# Sheet1.net
KiCad netlist of a schematic drawn in Altium Designer
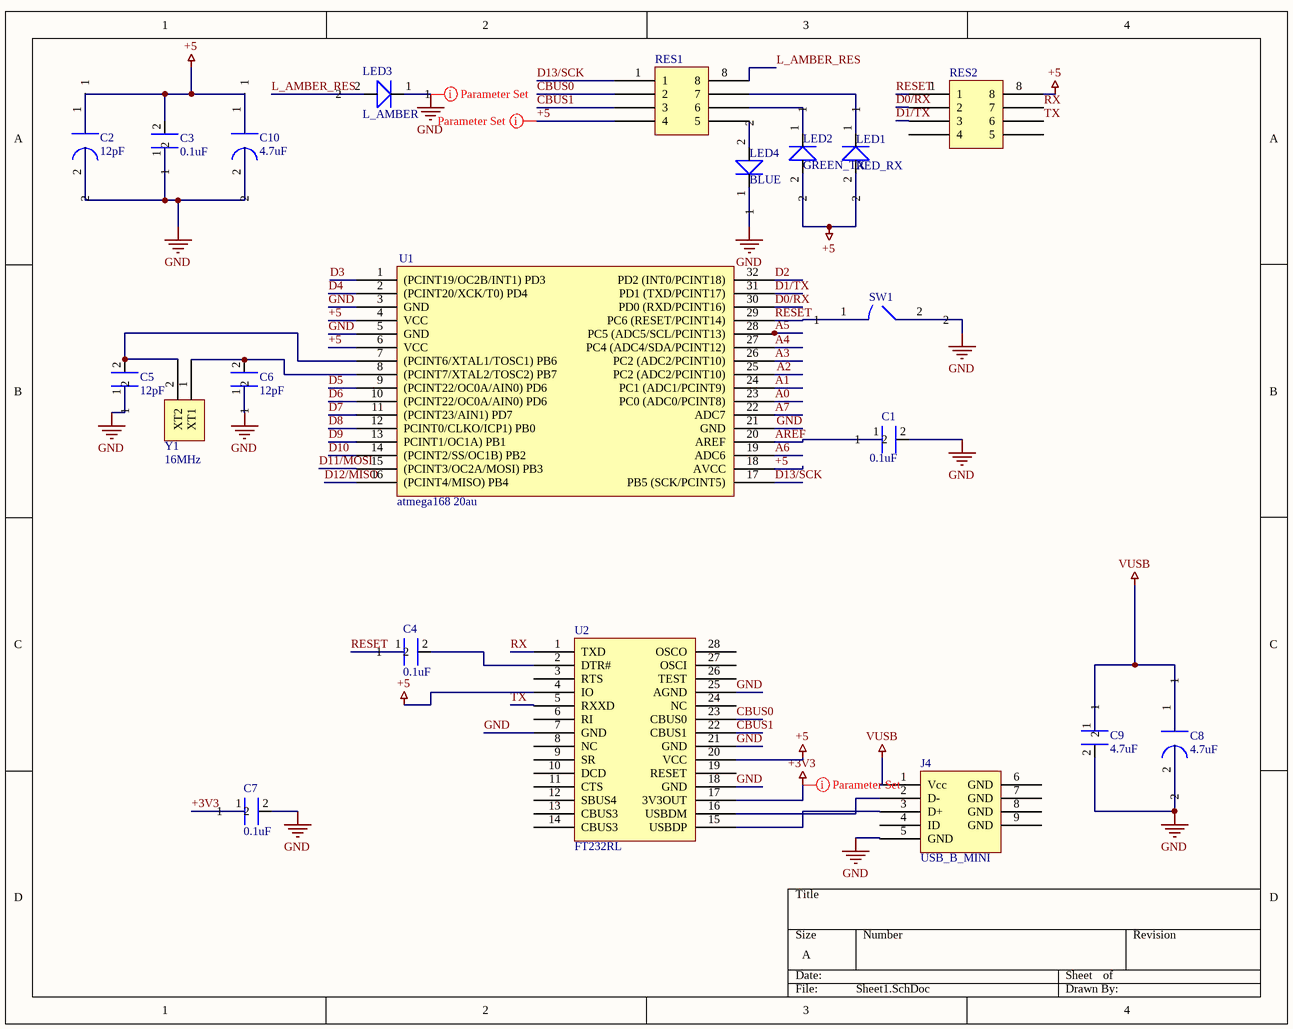
[diagram p0: Sheet1.SchDoc]

(export (version "E")
  (design (tool "Eeschema 10.0.6"))
  (components
    (comp (ref "C1") (value "0.1uF") (footprint "Capacitor0805") (libsource (lib "cap") (part "Component_1")))
    (comp (ref "C2")
      (value "12pF")
      (footprint "tantalum cap 7343")
      (libsource (lib "cap_pol") (part "Component_1"))
    )
    (comp (ref "C3") (value "0.1uF") (footprint "Capacitor0805") (libsource (lib "cap") (part "Component_1")))
    (comp (ref "C4") (value "0.1uF") (footprint "Capacitor0805") (libsource (lib "cap") (part "Component_1")))
    (comp (ref "C5") (value "12pF") (footprint "Capacitor0805") (libsource (lib "cap") (part "Component_1")))
    (comp (ref "C6") (value "12pF") (footprint "Capacitor0805") (libsource (lib "cap") (part "Component_1")))
    (comp (ref "C7") (value "0.1uF") (footprint "Capacitor0805") (libsource (lib "cap") (part "Component_1")))
    (comp (ref "C8")
      (value "4.7uF")
      (footprint "tantalum cap 7343")
      (libsource (lib "cap_pol") (part "Component_1"))
    )
    (comp (ref "C9") (value "4.7uF") (footprint "Capacitor0805") (libsource (lib "cap") (part "Component_1")))
    (comp (ref "C10")
      (value "4.7uF")
      (footprint "tantalum cap 7343")
      (libsource (lib "cap_pol") (part "Component_1"))
    )
    (comp (ref "J4")
      (value "USB_B_MINI")
      (footprint "Mini B usb")
      (libsource (lib "mini_USB_connector") (part "Component_1"))
    )
    (comp (ref "LED1") (value "RED_RX") (footprint "LED 0805") (libsource (lib "LED") (part "Component_1")))
    (comp (ref "LED2") (value "GREEN_TX") (footprint "LED 0805") (libsource (lib "LED") (part "Component_1")))
    (comp (ref "LED3") (value "L_AMBER") (footprint "LED 0805") (libsource (lib "LED") (part "Component_1")))
    (comp (ref "LED4") (value "BLUE") (footprint "LED 0805") (libsource (lib "LED") (part "Component_1")))
    (comp (ref "RES1")
      (value "Component_1")
      (footprint "Quad 4 res array")
      (libsource (lib "RES_ARRAY") (part "Component_1"))
    )
    (comp (ref "RES2")
      (value "Component_1")
      (footprint "Quad 4 res array")
      (libsource (lib "RES_ARRAY") (part "Component_1"))
    )
    (comp (ref "SW1") (value "RESET") (footprint "switch") (libsource (lib "switch") (part "Component_1")))
    (comp (ref "U1")
      (value "atmega168 20au")
      (footprint "Quad32")
      (libsource (lib "atmega16820au") (part "atmega168 20au"))
    )
    (comp (ref "U2")
      (value "FT232RL")
      (footprint "Quad28 FTDI")
      (libsource (lib "_REEL") (part "Component_1"))
    )
    (comp (ref "Y1") (value "16MHz") (footprint "TH XT") (libsource (lib "osci") (part "Component_1")))
  )
  (nets
    (net (code "1") (name "+3V3") (class "Default")
      (node (ref "C7") (pin "1") (pinfunction "1_1") (pintype "passive"))
      (node (ref "U2") (pin "17") (pinfunction "3V3OUT_17") (pintype "passive"))
    )
    (net (code "2") (name "+5") (class "Default")
      (node (ref "C10") (pin "1") (pinfunction "1_1") (pintype "passive"))
      (node (ref "C2") (pin "1") (pinfunction "1_1") (pintype "passive"))
      (node (ref "C3") (pin "2") (pinfunction "2_2") (pintype "passive"))
      (node (ref "LED1") (pin "2") (pinfunction "2_2") (pintype "passive"))
      (node (ref "LED2") (pin "2") (pinfunction "2_2") (pintype "passive"))
      (node (ref "RES1") (pin "4") (pinfunction "4_4") (pintype "passive"))
      (node (ref "RES2") (pin "8") (pinfunction "8_8") (pintype "passive"))
      (node (ref "U1") (pin "18") (pinfunction "AVCC_18") (pintype "passive"))
      (node (ref "U1") (pin "4") (pinfunction "VCC_4") (pintype "passive"))
      (node (ref "U1") (pin "6") (pinfunction "VCC_6") (pintype "passive"))
      (node (ref "U2") (pin "20") (pinfunction "VCC_20") (pintype "passive"))
      (node (ref "U2") (pin "4") (pinfunction "IO_4") (pintype "passive"))
    )
    (net (code "3") (name "/A0") (class "Default")
      (node (ref "U1") (pin "23") (pinfunction "PC0_(ADC0/PCINT8)_23") (pintype "passive"))
    )
    (net (code "4") (name "/A1") (class "Default")
      (node (ref "U1") (pin "24") (pinfunction "PC1_(ADC1/PCINT9)_24") (pintype "passive"))
    )
    (net (code "5") (name "/A2") (class "Default")
      (node (ref "U1") (pin "25") (pinfunction "PC2_(ADC2/PCINT10)_25") (pintype "passive"))
    )
    (net (code "6") (name "/A3") (class "Default")
      (node (ref "U1") (pin "26") (pinfunction "PC2_(ADC2/PCINT10)_26") (pintype "passive"))
    )
    (net (code "7") (name "/A4") (class "Default")
      (node (ref "U1") (pin "27") (pinfunction "PC4_(ADC4/SDA/PCINT12)_27") (pintype "passive"))
    )
    (net (code "8") (name "/A5") (class "Default")
      (node (ref "U1") (pin "28") (pinfunction "PC5_(ADC5/SCL/PCINT13)_28") (pintype "passive"))
    )
    (net (code "9") (name "/A6") (class "Default")
      (node (ref "U1") (pin "19") (pinfunction "ADC6_19") (pintype "passive"))
    )
    (net (code "10") (name "/A7") (class "Default")
      (node (ref "U1") (pin "22") (pinfunction "ADC7_22") (pintype "passive"))
    )
    (net (code "11") (name "/AREF") (class "Default")
      (node (ref "C1") (pin "1") (pinfunction "1_1") (pintype "passive"))
      (node (ref "U1") (pin "20") (pinfunction "AREF_20") (pintype "passive"))
    )
    (net (code "12") (name "/CBUS0") (class "Default")
      (node (ref "RES1") (pin "2") (pinfunction "2_2") (pintype "passive"))
      (node (ref "U2") (pin "23") (pinfunction "CBUS0_23") (pintype "passive"))
    )
    (net (code "13") (name "/CBUS1") (class "Default")
      (node (ref "RES1") (pin "3") (pinfunction "3_3") (pintype "passive"))
      (node (ref "U2") (pin "22") (pinfunction "CBUS1_22") (pintype "passive"))
    )
    (net (code "14") (name "/D0{slash}RX") (class "Default")
      (node (ref "RES2") (pin "2") (pinfunction "2_2") (pintype "passive"))
      (node (ref "U1") (pin "30") (pinfunction "PD0_(RXD/PCINT16)_30") (pintype "passive"))
    )
    (net (code "15") (name "/D1{slash}TX") (class "Default")
      (node (ref "RES2") (pin "3") (pinfunction "3_3") (pintype "passive"))
      (node (ref "U1") (pin "31") (pinfunction "PD1_(TXD/PCINT17)_31") (pintype "passive"))
    )
    (net (code "16") (name "/D2") (class "Default")
      (node (ref "U1") (pin "32") (pinfunction "PD2_(INT0/PCINT18)_32") (pintype "passive"))
    )
    (net (code "17") (name "/D3") (class "Default")
      (node (ref "U1") (pin "1") (pinfunction "(PCINT19/OC2B/INT1)_PD3_1") (pintype "passive"))
    )
    (net (code "18") (name "/D4") (class "Default")
      (node (ref "U1") (pin "2") (pinfunction "(PCINT20/XCK/T0)_PD4_2") (pintype "passive"))
    )
    (net (code "19") (name "/D5") (class "Default")
      (node (ref "U1") (pin "9") (pinfunction "(PCINT22/OC0A/AIN0)_PD6_9") (pintype "passive"))
    )
    (net (code "20") (name "/D6") (class "Default")
      (node (ref "U1") (pin "10") (pinfunction "(PCINT22/OC0A/AIN0)_PD6_10") (pintype "passive"))
    )
    (net (code "21") (name "/D7") (class "Default")
      (node (ref "U1") (pin "11") (pinfunction "(PCINT23/AIN1)_PD7_11") (pintype "passive"))
    )
    (net (code "22") (name "/D8") (class "Default")
      (node (ref "U1") (pin "12") (pinfunction "PCINT0/CLKO/ICP1)_PB0_12") (pintype "passive"))
    )
    (net (code "23") (name "/D9") (class "Default")
      (node (ref "U1") (pin "13") (pinfunction "PCINT1/OC1A)_PB1_13") (pintype "passive"))
    )
    (net (code "24") (name "/D10") (class "Default")
      (node (ref "U1") (pin "14") (pinfunction "(PCINT2/SS/OC1B)_PB2_14") (pintype "passive"))
    )
    (net (code "25") (name "/D11{slash}MOSI") (class "Default")
      (node (ref "U1") (pin "15") (pinfunction "(PCINT3/OC2A/MOSI)_PB3_15") (pintype "passive"))
    )
    (net (code "26") (name "/D12{slash}MISO") (class "Default")
      (node (ref "U1") (pin "16") (pinfunction "(PCINT4/MISO)_PB4_16") (pintype "passive"))
    )
    (net (code "27") (name "/D13{slash}SCK") (class "Default")
      (node (ref "RES1") (pin "1") (pinfunction "1_1") (pintype "passive"))
      (node (ref "U1") (pin "17") (pinfunction "PB5_(SCK/PCINT5)_17") (pintype "passive"))
    )
    (net (code "28") (name "/L_AMBER_RES") (class "Default")
      (node (ref "LED3") (pin "2") (pinfunction "2_2") (pintype "passive"))
      (node (ref "RES1") (pin "8") (pinfunction "8_8") (pintype "passive"))
    )
    (net (code "29") (name "/RESET") (class "Default")
      (node (ref "C4") (pin "1") (pinfunction "1_1") (pintype "passive"))
      (node (ref "RES2") (pin "1") (pinfunction "1_1") (pintype "passive"))
      (node (ref "SW1") (pin "1") (pinfunction "1_1") (pintype "passive"))
      (node (ref "U1") (pin "29") (pinfunction "PC6_(RESET/PCINT14)_29") (pintype "passive"))
    )
    (net (code "30") (name "/RX") (class "Default")
      (node (ref "RES2") (pin "7") (pinfunction "7_7") (pintype "passive"))
      (node (ref "U2") (pin "1") (pinfunction "TXD_1") (pintype "passive"))
    )
    (net (code "31") (name "/TX") (class "Default")
      (node (ref "RES2") (pin "6") (pinfunction "6_6") (pintype "passive"))
      (node (ref "U2") (pin "5") (pinfunction "RXXD_5") (pintype "passive"))
    )
    (net (code "32") (name "GND") (class "Default")
      (node (ref "C1") (pin "2") (pinfunction "2_2") (pintype "passive"))
      (node (ref "C10") (pin "2") (pinfunction "2_2") (pintype "passive"))
      (node (ref "C2") (pin "2") (pinfunction "2_2") (pintype "passive"))
      (node (ref "C3") (pin "1") (pinfunction "1_1") (pintype "passive"))
      (node (ref "C5") (pin "1") (pinfunction "1_1") (pintype "passive"))
      (node (ref "C6") (pin "1") (pinfunction "1_1") (pintype "passive"))
      (node (ref "C7") (pin "2") (pinfunction "2_2") (pintype "passive"))
      (node (ref "C8") (pin "2") (pinfunction "2_2") (pintype "passive"))
      (node (ref "C9") (pin "2") (pinfunction "2_2") (pintype "passive"))
      (node (ref "J4") (pin "5") (pinfunction "GND_5") (pintype "passive"))
      (node (ref "LED3") (pin "1") (pinfunction "1_1") (pintype "passive"))
      (node (ref "LED4") (pin "1") (pinfunction "1_1") (pintype "passive"))
      (node (ref "SW1") (pin "2") (pinfunction "2_2") (pintype "passive"))
      (node (ref "U1") (pin "21") (pinfunction "GND_21") (pintype "passive"))
      (node (ref "U1") (pin "3") (pinfunction "GND_3") (pintype "passive"))
      (node (ref "U1") (pin "5") (pinfunction "GND_5") (pintype "passive"))
      (node (ref "U2") (pin "18") (pinfunction "GND_18") (pintype "passive"))
      (node (ref "U2") (pin "21") (pinfunction "GND_21") (pintype "passive"))
      (node (ref "U2") (pin "25") (pinfunction "AGND_25") (pintype "passive"))
      (node (ref "U2") (pin "7") (pinfunction "GND_7") (pintype "passive"))
    )
    (net (code "33") (name "Net-(J4-D+)") (class "Default")
      (node (ref "J4") (pin "3") (pinfunction "D+_3") (pintype "passive"))
      (node (ref "U2") (pin "15") (pinfunction "USBDP_15") (pintype "passive"))
    )
    (net (code "34") (name "Net-(J4-D-)") (class "Default")
      (node (ref "J4") (pin "2") (pinfunction "D-_2") (pintype "passive"))
      (node (ref "U2") (pin "16") (pinfunction "USBDM_16") (pintype "passive"))
    )
    (net (code "35") (name "Net-(LED1-Pad1)") (class "Default")
      (node (ref "LED1") (pin "1") (pinfunction "1_1") (pintype "passive"))
      (node (ref "RES1") (pin "7") (pinfunction "7_7") (pintype "passive"))
    )
    (net (code "36") (name "Net-(LED2-Pad1)") (class "Default")
      (node (ref "LED2") (pin "1") (pinfunction "1_1") (pintype "passive"))
      (node (ref "RES1") (pin "6") (pinfunction "6_6") (pintype "passive"))
    )
    (net (code "37") (name "Net-(LED4-Pad2)") (class "Default")
      (node (ref "LED4") (pin "2") (pinfunction "2_2") (pintype "passive"))
      (node (ref "RES1") (pin "5") (pinfunction "5_5") (pintype "passive"))
    )
    (net (code "38") (name "Net-(U1-(PCINT6{slash}XTAL1{slash}TOSC1)_PB6)") (class "Default")
      (node (ref "C5") (pin "2") (pinfunction "2_2") (pintype "passive"))
      (node (ref "U1") (pin "7") (pinfunction "(PCINT6/XTAL1/TOSC1)_PB6_7") (pintype "passive"))
      (node (ref "Y1") (pin "2") (pinfunction "XT2_2") (pintype "passive"))
    )
    (net (code "39") (name "Net-(U1-(PCINT7{slash}XTAL2{slash}TOSC2)_PB7)") (class "Default")
      (node (ref "C6") (pin "2") (pinfunction "2_2") (pintype "passive"))
      (node (ref "U1") (pin "8") (pinfunction "(PCINT7/XTAL2/TOSC2)_PB7_8") (pintype "passive"))
      (node (ref "Y1") (pin "1") (pinfunction "XT1_1") (pintype "passive"))
    )
    (net (code "40") (name "Net-(U2-DTR#)") (class "Default")
      (node (ref "C4") (pin "2") (pinfunction "2_2") (pintype "passive"))
      (node (ref "U2") (pin "2") (pinfunction "DTR#_2") (pintype "passive"))
    )
    (net (code "41") (name "VUSB") (class "Default")
      (node (ref "C8") (pin "1") (pinfunction "1_1") (pintype "passive"))
      (node (ref "C9") (pin "1") (pinfunction "1_1") (pintype "passive"))
      (node (ref "J4") (pin "1") (pinfunction "Vcc_1") (pintype "passive"))
    )
    (net (code "42") (name "unconnected-(J4-GND-Pad6)") (class "Default")
      (node (ref "J4") (pin "6") (pinfunction "GND_6") (pintype "passive"))
    )
    (net (code "43") (name "unconnected-(J4-GND-Pad7)") (class "Default")
      (node (ref "J4") (pin "7") (pinfunction "GND_7") (pintype "passive"))
    )
    (net (code "44") (name "unconnected-(J4-GND-Pad8)") (class "Default")
      (node (ref "J4") (pin "8") (pinfunction "GND_8") (pintype "passive"))
    )
    (net (code "45") (name "unconnected-(J4-GND-Pad9)") (class "Default")
      (node (ref "J4") (pin "9") (pinfunction "GND_9") (pintype "passive"))
    )
    (net (code "46") (name "unconnected-(J4-ID-Pad4)") (class "Default")
      (node (ref "J4") (pin "4") (pinfunction "ID_4") (pintype "passive"))
    )
    (net (code "47") (name "unconnected-(RES2-Pad4)") (class "Default")
      (node (ref "RES2") (pin "4") (pinfunction "4_4") (pintype "passive"))
    )
    (net (code "48") (name "unconnected-(RES2-Pad5)") (class "Default")
      (node (ref "RES2") (pin "5") (pinfunction "5_5") (pintype "passive"))
    )
    (net (code "49") (name "unconnected-(U2-CBUS3-Pad13)") (class "Default")
      (node (ref "U2") (pin "13") (pinfunction "CBUS3_13") (pintype "passive"))
    )
    (net (code "50") (name "unconnected-(U2-CBUS3-Pad14)") (class "Default")
      (node (ref "U2") (pin "14") (pinfunction "CBUS3_14") (pintype "passive"))
    )
    (net (code "51") (name "unconnected-(U2-CTS-Pad11)") (class "Default")
      (node (ref "U2") (pin "11") (pinfunction "CTS_11") (pintype "passive"))
    )
    (net (code "52") (name "unconnected-(U2-DCD-Pad10)") (class "Default")
      (node (ref "U2") (pin "10") (pinfunction "DCD_10") (pintype "passive"))
    )
    (net (code "53") (name "unconnected-(U2-NC-Pad8)") (class "Default")
      (node (ref "U2") (pin "8") (pinfunction "NC_8") (pintype "passive"))
    )
    (net (code "54") (name "unconnected-(U2-NC-Pad24)") (class "Default")
      (node (ref "U2") (pin "24") (pinfunction "NC_24") (pintype "passive"))
    )
    (net (code "55") (name "unconnected-(U2-OSCI-Pad27)") (class "Default")
      (node (ref "U2") (pin "27") (pinfunction "OSCI_27") (pintype "passive"))
    )
    (net (code "56") (name "unconnected-(U2-OSCO-Pad28)") (class "Default")
      (node (ref "U2") (pin "28") (pinfunction "OSCO_28") (pintype "passive"))
    )
    (net (code "57") (name "unconnected-(U2-RESET-Pad19)") (class "Default")
      (node (ref "U2") (pin "19") (pinfunction "RESET_19") (pintype "passive"))
    )
    (net (code "58") (name "unconnected-(U2-RI-Pad6)") (class "Default")
      (node (ref "U2") (pin "6") (pinfunction "RI_6") (pintype "passive"))
    )
    (net (code "59") (name "unconnected-(U2-RTS-Pad3)") (class "Default")
      (node (ref "U2") (pin "3") (pinfunction "RTS_3") (pintype "passive"))
    )
    (net (code "60") (name "unconnected-(U2-SBUS4-Pad12)") (class "Default")
      (node (ref "U2") (pin "12") (pinfunction "SBUS4_12") (pintype "passive"))
    )
    (net (code "61") (name "unconnected-(U2-SR-Pad9)") (class "Default")
      (node (ref "U2") (pin "9") (pinfunction "SR_9") (pintype "passive"))
    )
    (net (code "62") (name "unconnected-(U2-TEST-Pad26)") (class "Default")
      (node (ref "U2") (pin "26") (pinfunction "TEST_26") (pintype "passive"))
    )
  )
)
